# 004_Charger.net
KiCad netlist of a schematic drawn in Altium Designer
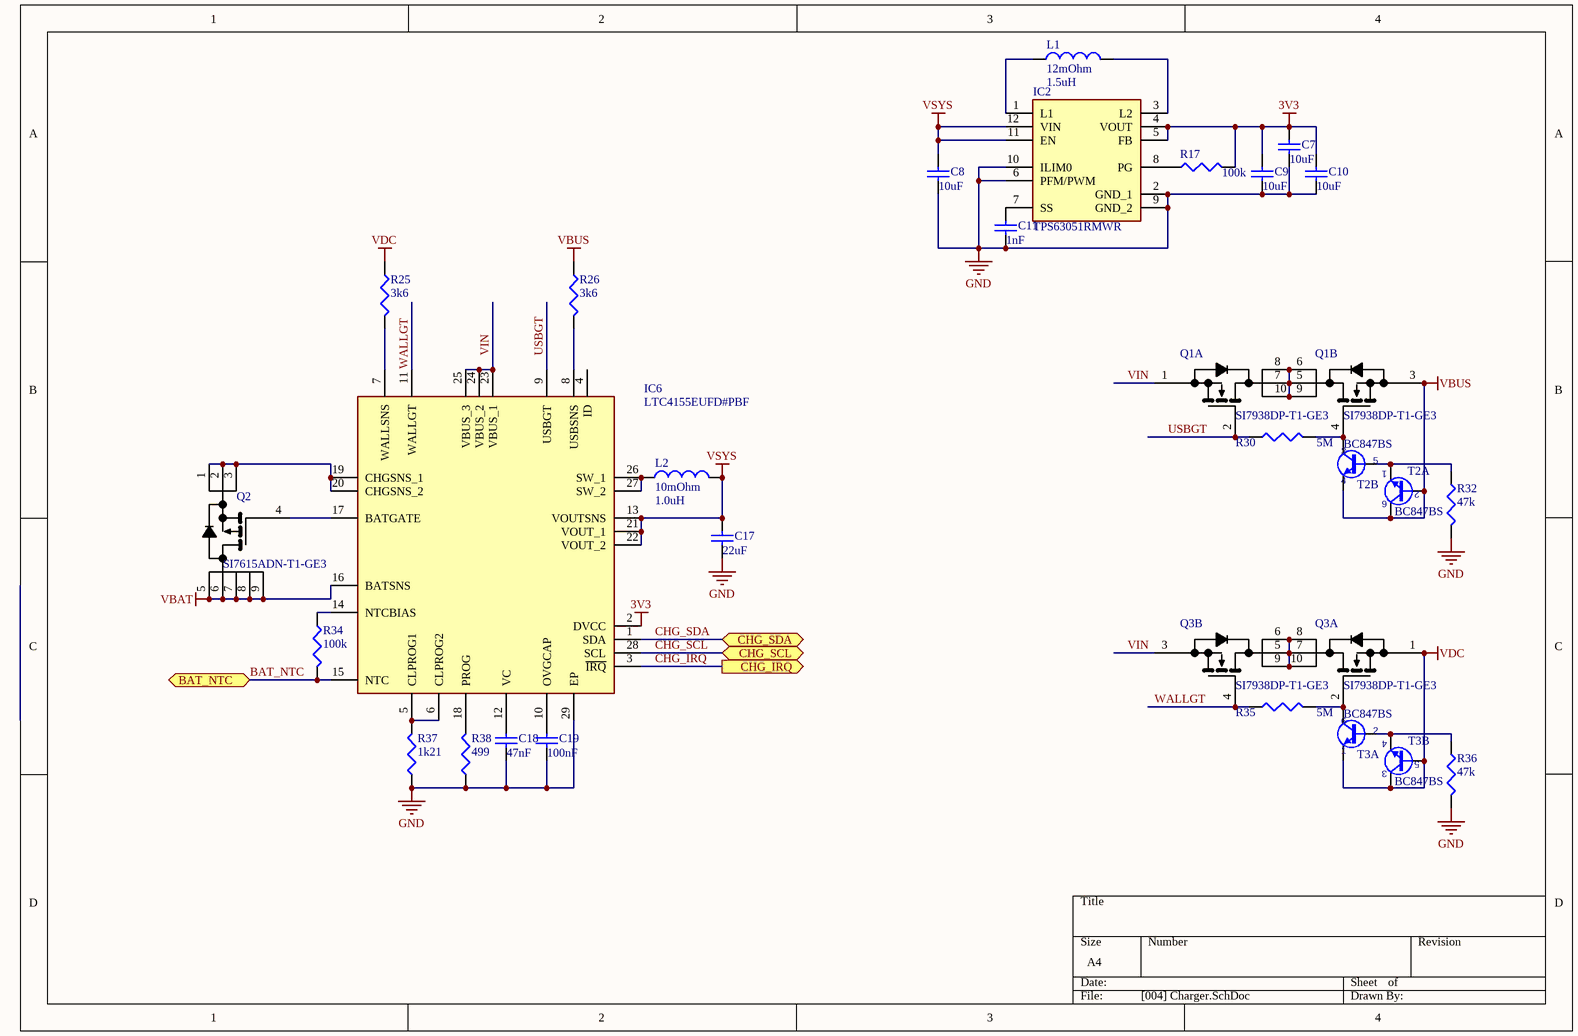
[diagram p0: [004] Charger.SchDoc]

(export (version "E")
  (design (tool "Eeschema 10.0.6"))
  (components
    (comp (ref "C7")
      (value "10uF")
      (footprint "1608[0603]")
      (description "Capacitor (Semiconductor SIM Model)")
      (fields (field (name "Comment") "Cap Semi") (field (name "PUBLISHER") "Altium Limited"))
      (libsource (lib "Miscellaneous Devices") (part "Cap Semi"))
    )
    (comp (ref "C8")
      (value "10uF")
      (footprint "1608[0603]")
      (description "Capacitor (Semiconductor SIM Model)")
      (fields (field (name "Comment") "Cap Semi") (field (name "PUBLISHER") "Altium Limited"))
      (libsource (lib "Miscellaneous Devices") (part "Cap Semi"))
    )
    (comp (ref "C9")
      (value "10uF")
      (footprint "1608[0603]")
      (description "Capacitor (Semiconductor SIM Model)")
      (fields (field (name "Comment") "Cap Semi") (field (name "PUBLISHER") "Altium Limited"))
      (libsource (lib "Miscellaneous Devices") (part "Cap Semi"))
    )
    (comp (ref "C10")
      (value "10uF")
      (footprint "1608[0603]")
      (description "Capacitor (Semiconductor SIM Model)")
      (fields (field (name "Comment") "Cap Semi") (field (name "PUBLISHER") "Altium Limited"))
      (libsource (lib "Miscellaneous Devices") (part "Cap Semi"))
    )
    (comp (ref "C11")
      (value "1nF")
      (footprint "1608[0603]")
      (description "Capacitor (Semiconductor SIM Model)")
      (fields (field (name "Comment") "Cap Semi") (field (name "PUBLISHER") "Altium Limited"))
      (libsource (lib "Miscellaneous Devices") (part "Cap Semi"))
    )
    (comp (ref "C17")
      (value "22uF")
      (footprint "1608[0603]")
      (description "Capacitor (Semiconductor SIM Model)")
      (fields (field (name "Comment") "Cap Semi") (field (name "PUBLISHER") "Altium Limited"))
      (libsource (lib "Miscellaneous Devices") (part "Cap Semi"))
    )
    (comp (ref "C18")
      (value "47nF")
      (footprint "1608[0603]")
      (description "Capacitor (Semiconductor SIM Model)")
      (fields (field (name "Comment") "Cap Semi") (field (name "PUBLISHER") "Altium Limited"))
      (libsource (lib "Miscellaneous Devices") (part "Cap Semi"))
    )
    (comp (ref "C19")
      (value "100nF")
      (footprint "1608[0603]")
      (description "Capacitor (Semiconductor SIM Model)")
      (fields (field (name "Comment") "Cap Semi") (field (name "PUBLISHER") "Altium Limited"))
      (libsource (lib "Miscellaneous Devices") (part "Cap Semi"))
    )
    (comp (ref "IC2")
      (value "TPS63051RMWR")
      (footprint "SamacSys:QFN50P250X250X100-12N-D")
      (description "Integrated Circuit")
      (libsource (lib "SamacSys") (part "TPS63051RMWR"))
    )
    (comp (ref "IC6")
      (value "LTC4155EUFD#PBF")
      (footprint "SamacSys:QFN50P400X500X80-29N-D")
      (description "Integrated Circuit")
      (libsource (lib "SamacSys") (part "LTC4155EUFD#PBF"))
    )
    (comp (ref "L1")
      (value "12mOhm")
      (footprint "INDP2523X23N")
      (description "Inductor SRN6045TA-1R5Y")
      (fields (field (name "ALTIUM_VALUE") "1.5uH") (field (name "PUBLISHER") "Altium Limited"))
      (libsource (lib "Miscellaneous Devices") (part "Inductor"))
    )
    (comp (ref "L2")
      (value "10mOhm")
      (footprint "INDP2523X23N")
      (description "Inductor SRN6045TA-1R0Y")
      (fields (field (name "ALTIUM_VALUE") "1.0uH") (field (name "PUBLISHER") "Altium Limited"))
      (libsource (lib "Miscellaneous Devices") (part "Inductor"))
    )
    (comp (ref "Q1")
      (value "SI7938DP-T1-GE3")
      (footprint "SamacSys:POWERPAK-SO8_1")
      (description "MOSFET (N-Channel)")
      (libsource (lib "SamacSys") (part "SI7938DP-T1-GE3"))
    )
    (comp (ref "Q2")
      (value "SI7615ADN-T1-GE3")
      (footprint "SamacSys:PowerPAK1212-8 Single")
      (description "MOSFET (P-Channel)")
      (fields (field (name "MANUFACTURER_PART_NUMBER") "SIS413DN-T1-GE3"))
      (libsource (lib "SamacSys") (part "SI7615ADN-T1-GE3"))
    )
    (comp (ref "Q3")
      (value "SI7938DP-T1-GE3")
      (footprint "SamacSys:POWERPAK-SO8_1")
      (description "MOSFET (N-Channel)")
      (libsource (lib "SamacSys") (part "SI7938DP-T1-GE3"))
    )
    (comp (ref "R17")
      (value "100k")
      (footprint "J1-0603")
      (description "Resistor")
      (fields (field (name "Comment") "Res3") (field (name "PUBLISHER") "Altium Limited"))
      (libsource (lib "Miscellaneous Devices") (part "Res3"))
    )
    (comp (ref "R25")
      (value "3k6")
      (footprint "J1-0603")
      (description "Resistor")
      (fields (field (name "Comment") "Res3") (field (name "PUBLISHER") "Altium Limited"))
      (libsource (lib "Miscellaneous Devices") (part "Res3"))
    )
    (comp (ref "R26")
      (value "3k6")
      (footprint "J1-0603")
      (description "Resistor")
      (fields (field (name "Comment") "Res3") (field (name "PUBLISHER") "Altium Limited"))
      (libsource (lib "Miscellaneous Devices") (part "Res3"))
    )
    (comp (ref "R30")
      (value "5M")
      (footprint "J1-0603")
      (description "Resistor")
      (fields (field (name "Comment") "Res3") (field (name "PUBLISHER") "Altium Limited"))
      (libsource (lib "Miscellaneous Devices") (part "Res3"))
    )
    (comp (ref "R32")
      (value "47k")
      (footprint "J1-0603")
      (description "Resistor")
      (fields (field (name "Comment") "Res3") (field (name "PUBLISHER") "Altium Limited"))
      (libsource (lib "Miscellaneous Devices") (part "Res3"))
    )
    (comp (ref "R34")
      (value "100k")
      (footprint "J1-0603")
      (description "Resistor")
      (fields (field (name "Comment") "Res3") (field (name "PUBLISHER") "Altium Limited"))
      (libsource (lib "Miscellaneous Devices") (part "Res3"))
    )
    (comp (ref "R35")
      (value "5M")
      (footprint "J1-0603")
      (description "Resistor")
      (fields (field (name "Comment") "Res3") (field (name "PUBLISHER") "Altium Limited"))
      (libsource (lib "Miscellaneous Devices") (part "Res3"))
    )
    (comp (ref "R36")
      (value "47k")
      (footprint "J1-0603")
      (description "Resistor")
      (fields (field (name "Comment") "Res3") (field (name "PUBLISHER") "Altium Limited"))
      (libsource (lib "Miscellaneous Devices") (part "Res3"))
    )
    (comp (ref "R37")
      (value "1k21")
      (footprint "J1-0603")
      (description "Resistor")
      (fields (field (name "Comment") "Res3") (field (name "PUBLISHER") "Altium Limited"))
      (libsource (lib "Miscellaneous Devices") (part "Res3"))
    )
    (comp (ref "R38")
      (value "499")
      (footprint "J1-0603")
      (description "Resistor")
      (fields (field (name "Comment") "Res3") (field (name "PUBLISHER") "Altium Limited"))
      (libsource (lib "Miscellaneous Devices") (part "Res3"))
    )
    (comp (ref "T2")
      (value "BC847BS")
      (footprint "SOT65P210X110-6N")
      (description "45V 100mA Dual NPN General-Purpose Transistor")
      (fields (field (name "MANUFACTURER") "NXP SEMICONDUCTORS") (field (name "AUTHOR") "CERN DEM JMW"))
      (libsource (lib "") (part "BC847BS_1"))
    )
    (comp (ref "T3")
      (value "BC847BS")
      (footprint "SOT65P210X110-6N")
      (description "45V 100mA Dual NPN General-Purpose Transistor")
      (fields (field (name "MANUFACTURER") "NXP SEMICONDUCTORS") (field (name "AUTHOR") "CERN DEM JMW"))
      (libsource (lib "ICs And Semiconductors") (part "BC847BS"))
    )
  )
  (nets
    (net (code "1") (name "/BAT_NTC") (class "Default")
      (node (ref "IC6") (pin "15") (pinfunction "NTC_15") (pintype "passive"))
      (node (ref "R34") (pin "2") (pinfunction "2_2") (pintype "passive"))
    )
    (net (code "2") (name "/CHG_IRQ") (class "Default")
      (node (ref "IC6") (pin "3") (pinfunction "~{IRQ}_3") (pintype "passive"))
    )
    (net (code "3") (name "/CHG_SCL") (class "Default")
      (node (ref "IC6") (pin "28") (pinfunction "SCL_28") (pintype "passive"))
    )
    (net (code "4") (name "/CHG_SDA") (class "Default")
      (node (ref "IC6") (pin "1") (pinfunction "SDA_1") (pintype "passive"))
    )
    (net (code "5") (name "/USBGT") (class "Default")
      (node (ref "IC6") (pin "9") (pinfunction "USBGT_9") (pintype "passive"))
      (node (ref "Q1") (pin "2") (pinfunction "G1_2") (pintype "passive"))
      (node (ref "R30") (pin "1") (pinfunction "1_1") (pintype "passive"))
    )
    (net (code "6") (name "/VIN") (class "Default")
      (node (ref "IC6") (pin "23") (pinfunction "VBUS_1_23") (pintype "passive"))
      (node (ref "IC6") (pin "24") (pinfunction "VBUS_2_24") (pintype "passive"))
      (node (ref "IC6") (pin "25") (pinfunction "VBUS_3_25") (pintype "passive"))
      (node (ref "Q1") (pin "1") (pinfunction "S1_1") (pintype "passive"))
      (node (ref "Q3") (pin "3") (pinfunction "S2_3") (pintype "passive"))
    )
    (net (code "7") (name "/WALLGT") (class "Default")
      (node (ref "IC6") (pin "11") (pinfunction "WALLGT_11") (pintype "passive"))
      (node (ref "Q3") (pin "4") (pinfunction "G2_4") (pintype "passive"))
      (node (ref "R35") (pin "1") (pinfunction "1_1") (pintype "passive"))
    )
    (net (code "8") (name "3V3") (class "Default")
      (node (ref "C10") (pin "2") (pinfunction "2_2") (pintype "passive"))
      (node (ref "C7") (pin "2") (pinfunction "2_2") (pintype "passive"))
      (node (ref "C9") (pin "2") (pinfunction "2_2") (pintype "passive"))
      (node (ref "IC2") (pin "4") (pinfunction "VOUT_4") (pintype "passive"))
      (node (ref "IC2") (pin "5") (pinfunction "FB_5") (pintype "passive"))
      (node (ref "IC6") (pin "2") (pinfunction "DVCC_2") (pintype "passive"))
      (node (ref "R17") (pin "2") (pinfunction "2_2") (pintype "passive"))
    )
    (net (code "9") (name "GND") (class "Default")
      (node (ref "C10") (pin "1") (pinfunction "1_1") (pintype "passive"))
      (node (ref "C11") (pin "1") (pinfunction "1_1") (pintype "passive"))
      (node (ref "C17") (pin "1") (pinfunction "1_1") (pintype "passive"))
      (node (ref "C18") (pin "1") (pinfunction "1_1") (pintype "passive"))
      (node (ref "C19") (pin "1") (pinfunction "1_1") (pintype "passive"))
      (node (ref "C7") (pin "1") (pinfunction "1_1") (pintype "passive"))
      (node (ref "C8") (pin "1") (pinfunction "1_1") (pintype "passive"))
      (node (ref "C9") (pin "1") (pinfunction "1_1") (pintype "passive"))
      (node (ref "IC2") (pin "10") (pinfunction "ILIM0_10") (pintype "passive"))
      (node (ref "IC2") (pin "2") (pinfunction "GND_1_2") (pintype "passive"))
      (node (ref "IC2") (pin "6") (pinfunction "PFM/PWM_6") (pintype "passive"))
      (node (ref "IC2") (pin "9") (pinfunction "GND_2_9") (pintype "passive"))
      (node (ref "IC6") (pin "29") (pinfunction "EP_29") (pintype "passive"))
      (node (ref "R32") (pin "2") (pinfunction "2_2") (pintype "passive"))
      (node (ref "R36") (pin "2") (pinfunction "2_2") (pintype "passive"))
      (node (ref "R37") (pin "1") (pinfunction "1_1") (pintype "passive"))
      (node (ref "R38") (pin "1") (pinfunction "1_1") (pintype "passive"))
    )
    (net (code "10") (name "Net-(IC2-L1)") (class "Default")
      (node (ref "IC2") (pin "1") (pinfunction "L1_1") (pintype "passive"))
      (node (ref "L1") (pin "1") (pinfunction "1_1") (pintype "passive"))
    )
    (net (code "11") (name "Net-(IC2-L2)") (class "Default")
      (node (ref "IC2") (pin "3") (pinfunction "L2_3") (pintype "passive"))
      (node (ref "L1") (pin "2") (pinfunction "2_2") (pintype "passive"))
    )
    (net (code "12") (name "Net-(IC2-PG)") (class "Default")
      (node (ref "IC2") (pin "8") (pinfunction "PG_8") (pintype "passive"))
      (node (ref "R17") (pin "1") (pinfunction "1_1") (pintype "passive"))
    )
    (net (code "13") (name "Net-(IC2-SS)") (class "Default")
      (node (ref "C11") (pin "2") (pinfunction "2_2") (pintype "passive"))
      (node (ref "IC2") (pin "7") (pinfunction "SS_7") (pintype "passive"))
    )
    (net (code "14") (name "Net-(IC6-BATGATE)") (class "Default")
      (node (ref "IC6") (pin "17") (pinfunction "BATGATE_17") (pintype "passive"))
      (node (ref "Q2") (pin "4") (pinfunction "G_4") (pintype "passive"))
    )
    (net (code "15") (name "Net-(IC6-CHGSNS_1)") (class "Default")
      (node (ref "IC6") (pin "19") (pinfunction "CHGSNS_1_19") (pintype "passive"))
      (node (ref "IC6") (pin "20") (pinfunction "CHGSNS_2_20") (pintype "passive"))
      (node (ref "Q2") (pin "1") (pinfunction "S_1") (pintype "passive"))
      (node (ref "Q2") (pin "2") (pinfunction "S_2") (pintype "passive"))
      (node (ref "Q2") (pin "3") (pinfunction "S_3") (pintype "passive"))
    )
    (net (code "16") (name "Net-(IC6-CLPROG1)") (class "Default")
      (node (ref "IC6") (pin "5") (pinfunction "CLPROG1_5") (pintype "passive"))
      (node (ref "IC6") (pin "6") (pinfunction "CLPROG2_6") (pintype "passive"))
      (node (ref "R37") (pin "2") (pinfunction "2_2") (pintype "passive"))
    )
    (net (code "17") (name "Net-(IC6-NTCBIAS)") (class "Default")
      (node (ref "IC6") (pin "14") (pinfunction "NTCBIAS_14") (pintype "passive"))
      (node (ref "R34") (pin "1") (pinfunction "1_1") (pintype "passive"))
    )
    (net (code "18") (name "Net-(IC6-OVGCAP)") (class "Default")
      (node (ref "C19") (pin "2") (pinfunction "2_2") (pintype "passive"))
      (node (ref "IC6") (pin "10") (pinfunction "OVGCAP_10") (pintype "passive"))
    )
    (net (code "19") (name "Net-(IC6-PROG)") (class "Default")
      (node (ref "IC6") (pin "18") (pinfunction "PROG_18") (pintype "passive"))
      (node (ref "R38") (pin "2") (pinfunction "2_2") (pintype "passive"))
    )
    (net (code "20") (name "Net-(IC6-SW_1)") (class "Default")
      (node (ref "IC6") (pin "26") (pinfunction "SW_1_26") (pintype "passive"))
      (node (ref "IC6") (pin "27") (pinfunction "SW_2_27") (pintype "passive"))
      (node (ref "L2") (pin "1") (pinfunction "1_1") (pintype "passive"))
    )
    (net (code "21") (name "Net-(IC6-USBSNS)") (class "Default")
      (node (ref "IC6") (pin "8") (pinfunction "USBSNS_8") (pintype "passive"))
      (node (ref "R26") (pin "2") (pinfunction "2_2") (pintype "passive"))
    )
    (net (code "22") (name "Net-(IC6-VC)") (class "Default")
      (node (ref "C18") (pin "2") (pinfunction "2_2") (pintype "passive"))
      (node (ref "IC6") (pin "12") (pinfunction "VC_12") (pintype "passive"))
    )
    (net (code "23") (name "Net-(IC6-WALLSNS)") (class "Default")
      (node (ref "IC6") (pin "7") (pinfunction "WALLSNS_7") (pintype "passive"))
      (node (ref "R25") (pin "2") (pinfunction "2_2") (pintype "passive"))
    )
    (net (code "24") (name "Net-(Q1A-D1_1)") (class "Default")
      (node (ref "Q1") (pin "10") (pinfunction "D1_3_10") (pintype "passive"))
      (node (ref "Q1") (pin "5") (pinfunction "D2_1_5") (pintype "passive"))
      (node (ref "Q1") (pin "6") (pinfunction "D2_2_6") (pintype "passive"))
      (node (ref "Q1") (pin "7") (pinfunction "D1_1_7") (pintype "passive"))
      (node (ref "Q1") (pin "8") (pinfunction "D1_2_8") (pintype "passive"))
      (node (ref "Q1") (pin "9") (pinfunction "D2_3_9") (pintype "passive"))
    )
    (net (code "25") (name "Net-(Q1B-G2)") (class "Default")
      (node (ref "Q1") (pin "4") (pinfunction "G2_4") (pintype "passive"))
      (node (ref "R30") (pin "2") (pinfunction "2_2") (pintype "passive"))
      (node (ref "T2") (pin "3") (pinfunction "C_3") (pintype "passive"))
    )
    (net (code "26") (name "Net-(Q3A-D1_1)") (class "Default")
      (node (ref "Q3") (pin "10") (pinfunction "D1_3_10") (pintype "passive"))
      (node (ref "Q3") (pin "5") (pinfunction "D2_1_5") (pintype "passive"))
      (node (ref "Q3") (pin "6") (pinfunction "D2_2_6") (pintype "passive"))
      (node (ref "Q3") (pin "7") (pinfunction "D1_1_7") (pintype "passive"))
      (node (ref "Q3") (pin "8") (pinfunction "D1_2_8") (pintype "passive"))
      (node (ref "Q3") (pin "9") (pinfunction "D2_3_9") (pintype "passive"))
    )
    (net (code "27") (name "Net-(Q3A-G1)") (class "Default")
      (node (ref "Q3") (pin "2") (pinfunction "G1_2") (pintype "passive"))
      (node (ref "R35") (pin "2") (pinfunction "2_2") (pintype "passive"))
      (node (ref "T3") (pin "6") (pinfunction "C_6") (pintype "passive"))
    )
    (net (code "28") (name "Net-(T2A-E)") (class "Default")
      (node (ref "R32") (pin "1") (pinfunction "1_1") (pintype "passive"))
      (node (ref "T2") (pin "1") (pinfunction "E_1") (pintype "passive"))
      (node (ref "T2") (pin "5") (pinfunction "B_5") (pintype "passive"))
    )
    (net (code "29") (name "Net-(T3A-B)") (class "Default")
      (node (ref "R36") (pin "1") (pinfunction "1_1") (pintype "passive"))
      (node (ref "T3") (pin "2") (pinfunction "B_2") (pintype "passive"))
      (node (ref "T3") (pin "4") (pinfunction "E_4") (pintype "passive"))
    )
    (net (code "30") (name "VBAT") (class "Default")
      (node (ref "IC6") (pin "16") (pinfunction "BATSNS_16") (pintype "passive"))
      (node (ref "Q2") (pin "5") (pinfunction "D_5") (pintype "passive"))
      (node (ref "Q2") (pin "6") (pinfunction "D_6") (pintype "passive"))
      (node (ref "Q2") (pin "7") (pinfunction "D_7") (pintype "passive"))
      (node (ref "Q2") (pin "8") (pinfunction "D_8") (pintype "passive"))
      (node (ref "Q2") (pin "9") (pinfunction "D_9") (pintype "passive"))
    )
    (net (code "31") (name "VBUS") (class "Default")
      (node (ref "Q1") (pin "3") (pinfunction "S2_3") (pintype "passive"))
      (node (ref "R26") (pin "1") (pinfunction "1_1") (pintype "passive"))
      (node (ref "T2") (pin "2") (pinfunction "B_2") (pintype "passive"))
      (node (ref "T2") (pin "4") (pinfunction "E_4") (pintype "passive"))
      (node (ref "T2") (pin "6") (pinfunction "C_6") (pintype "passive"))
    )
    (net (code "32") (name "VDC") (class "Default")
      (node (ref "Q3") (pin "1") (pinfunction "S1_1") (pintype "passive"))
      (node (ref "R25") (pin "1") (pinfunction "1_1") (pintype "passive"))
      (node (ref "T3") (pin "1") (pinfunction "E_1") (pintype "passive"))
      (node (ref "T3") (pin "3") (pinfunction "C_3") (pintype "passive"))
      (node (ref "T3") (pin "5") (pinfunction "B_5") (pintype "passive"))
    )
    (net (code "33") (name "VSYS") (class "Default")
      (node (ref "C17") (pin "2") (pinfunction "2_2") (pintype "passive"))
      (node (ref "C8") (pin "2") (pinfunction "2_2") (pintype "passive"))
      (node (ref "IC2") (pin "11") (pinfunction "EN_11") (pintype "passive"))
      (node (ref "IC2") (pin "12") (pinfunction "VIN_12") (pintype "passive"))
      (node (ref "IC6") (pin "13") (pinfunction "VOUTSNS_13") (pintype "passive"))
      (node (ref "IC6") (pin "21") (pinfunction "VOUT_1_21") (pintype "passive"))
      (node (ref "IC6") (pin "22") (pinfunction "VOUT_2_22") (pintype "passive"))
      (node (ref "L2") (pin "2") (pinfunction "2_2") (pintype "passive"))
    )
    (net (code "34") (name "unconnected-(IC6-ID-Pad4)") (class "Default")
      (node (ref "IC6") (pin "4") (pinfunction "ID_4") (pintype "passive"))
    )
  )
)
